# ringmodulator.net
KiCad netlist of a schematic drawn in EAGLE
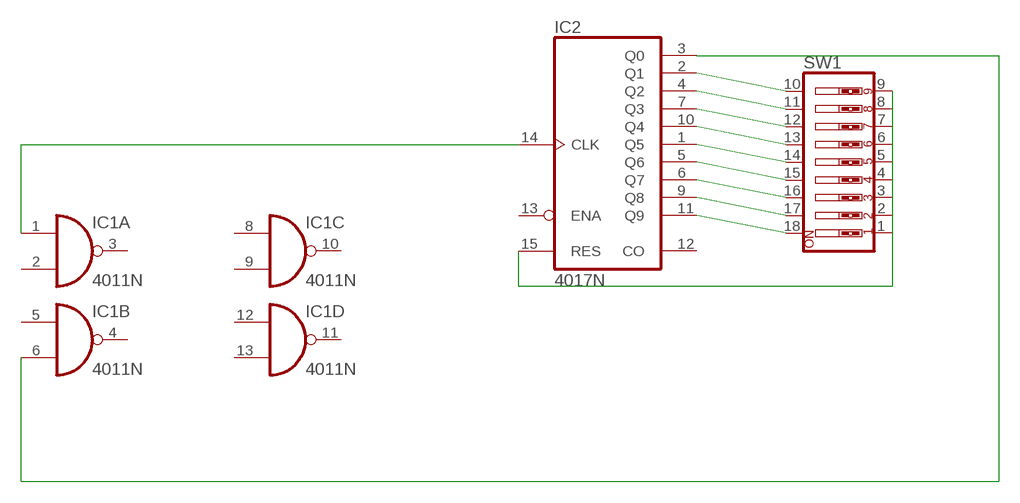
[diagram p0: schematic, sheet 1]

(export (version "E")
  (design (tool "Eeschema 10.0.6"))
  (components
    (comp (ref "IC1")
      (value "4011N")
      (footprint "eagle-import:DIL14")
      (libsource (lib "eagle-import") (part "4011N"))
    )
    (comp (ref "IC2")
      (value "4017N")
      (footprint "eagle-import:DIL16")
      (libsource (lib "eagle-import") (part "4017N"))
    )
    (comp (ref "SW1")
      (value "SW_DIP-9")
      (footprint "eagle-import:EDG-09")
      (libsource (lib "eagle-import") (part "SW_DIP-9"))
    )
  )
  (nets
    (net (code "1") (name "Net-(IC1A-I0)") (class "Default")
      (node (ref "IC1") (pin "1") (pinfunction "I0_1") (pintype "input"))
      (node (ref "IC2") (pin "14") (pinfunction "CLK_14") (pintype "input"))
    )
    (net (code "2") (name "Net-(IC1B-I1)") (class "Default")
      (node (ref "IC1") (pin "6") (pinfunction "I1_6") (pintype "input"))
      (node (ref "IC2") (pin "3") (pinfunction "Q0_3") (pintype "output"))
    )
    (net (code "3") (name "Net-(IC2A-Q1)") (class "Default")
      (node (ref "IC2") (pin "2") (pinfunction "Q1_2") (pintype "output"))
      (node (ref "SW1") (pin "10") (pinfunction "10_10") (pintype "passive"))
    )
    (net (code "4") (name "Net-(IC2A-Q2)") (class "Default")
      (node (ref "IC2") (pin "4") (pinfunction "Q2_4") (pintype "output"))
      (node (ref "SW1") (pin "11") (pinfunction "11_11") (pintype "passive"))
    )
    (net (code "5") (name "Net-(IC2A-Q3)") (class "Default")
      (node (ref "IC2") (pin "7") (pinfunction "Q3_7") (pintype "output"))
      (node (ref "SW1") (pin "12") (pinfunction "12_12") (pintype "passive"))
    )
    (net (code "6") (name "Net-(IC2A-Q4)") (class "Default")
      (node (ref "IC2") (pin "10") (pinfunction "Q4_10") (pintype "output"))
      (node (ref "SW1") (pin "13") (pinfunction "13_13") (pintype "passive"))
    )
    (net (code "7") (name "Net-(IC2A-Q5)") (class "Default")
      (node (ref "IC2") (pin "1") (pinfunction "Q5_1") (pintype "output"))
      (node (ref "SW1") (pin "14") (pinfunction "14_14") (pintype "passive"))
    )
    (net (code "8") (name "Net-(IC2A-Q6)") (class "Default")
      (node (ref "IC2") (pin "5") (pinfunction "Q6_5") (pintype "output"))
      (node (ref "SW1") (pin "15") (pinfunction "15_15") (pintype "passive"))
    )
    (net (code "9") (name "Net-(IC2A-Q7)") (class "Default")
      (node (ref "IC2") (pin "6") (pinfunction "Q7_6") (pintype "output"))
      (node (ref "SW1") (pin "16") (pinfunction "16_16") (pintype "passive"))
    )
    (net (code "10") (name "Net-(IC2A-Q8)") (class "Default")
      (node (ref "IC2") (pin "9") (pinfunction "Q8_9") (pintype "output"))
      (node (ref "SW1") (pin "17") (pinfunction "17_17") (pintype "passive"))
    )
    (net (code "11") (name "Net-(IC2A-Q9)") (class "Default")
      (node (ref "IC2") (pin "11") (pinfunction "Q9_11") (pintype "output"))
      (node (ref "SW1") (pin "18") (pinfunction "18_18") (pintype "passive"))
    )
    (net (code "12") (name "Net-(IC2A-RES)") (class "Default")
      (node (ref "IC2") (pin "15") (pinfunction "RES_15") (pintype "input"))
      (node (ref "SW1") (pin "1") (pinfunction "1_1") (pintype "passive"))
      (node (ref "SW1") (pin "2") (pinfunction "2_2") (pintype "passive"))
      (node (ref "SW1") (pin "3") (pinfunction "3_3") (pintype "passive"))
      (node (ref "SW1") (pin "4") (pinfunction "4_4") (pintype "passive"))
      (node (ref "SW1") (pin "5") (pinfunction "5_5") (pintype "passive"))
      (node (ref "SW1") (pin "6") (pinfunction "6_6") (pintype "passive"))
      (node (ref "SW1") (pin "7") (pinfunction "7_7") (pintype "passive"))
      (node (ref "SW1") (pin "8") (pinfunction "8_8") (pintype "passive"))
      (node (ref "SW1") (pin "9") (pinfunction "9_9") (pintype "passive"))
    )
    (net (code "13") (name "unconnected-(IC1A-I1-Pad2)") (class "Default")
      (node (ref "IC1") (pin "2") (pinfunction "I1_2") (pintype "input"))
    )
    (net (code "14") (name "unconnected-(IC1A-O-Pad3)") (class "Default")
      (node (ref "IC1") (pin "3") (pinfunction "O_3") (pintype "output"))
    )
    (net (code "15") (name "unconnected-(IC1B-I0-Pad5)") (class "Default")
      (node (ref "IC1") (pin "5") (pinfunction "I0_5") (pintype "input"))
    )
    (net (code "16") (name "unconnected-(IC1B-O-Pad4)") (class "Default")
      (node (ref "IC1") (pin "4") (pinfunction "O_4") (pintype "output"))
    )
    (net (code "17") (name "unconnected-(IC1C-I0-Pad8)") (class "Default")
      (node (ref "IC1") (pin "8") (pinfunction "I0_8") (pintype "input"))
    )
    (net (code "18") (name "unconnected-(IC1C-I1-Pad9)") (class "Default")
      (node (ref "IC1") (pin "9") (pinfunction "I1_9") (pintype "input"))
    )
    (net (code "19") (name "unconnected-(IC1C-O-Pad10)") (class "Default")
      (node (ref "IC1") (pin "10") (pinfunction "O_10") (pintype "output"))
    )
    (net (code "20") (name "unconnected-(IC1D-I0-Pad12)") (class "Default")
      (node (ref "IC1") (pin "12") (pinfunction "I0_12") (pintype "input"))
    )
    (net (code "21") (name "unconnected-(IC1D-I1-Pad13)") (class "Default")
      (node (ref "IC1") (pin "13") (pinfunction "I1_13") (pintype "input"))
    )
    (net (code "22") (name "unconnected-(IC1D-O-Pad11)") (class "Default")
      (node (ref "IC1") (pin "11") (pinfunction "O_11") (pintype "output"))
    )
    (net (code "23") (name "unconnected-(IC2A-CO-Pad12)") (class "Default")
      (node (ref "IC2") (pin "12") (pinfunction "CO_12") (pintype "output"))
    )
    (net (code "24") (name "unconnected-(IC2A-ENA-Pad13)") (class "Default")
      (node (ref "IC2") (pin "13") (pinfunction "ENA_13") (pintype "input"))
    )
  )
)
